# BoundaryController.net
KiCad netlist of a schematic drawn in EAGLE
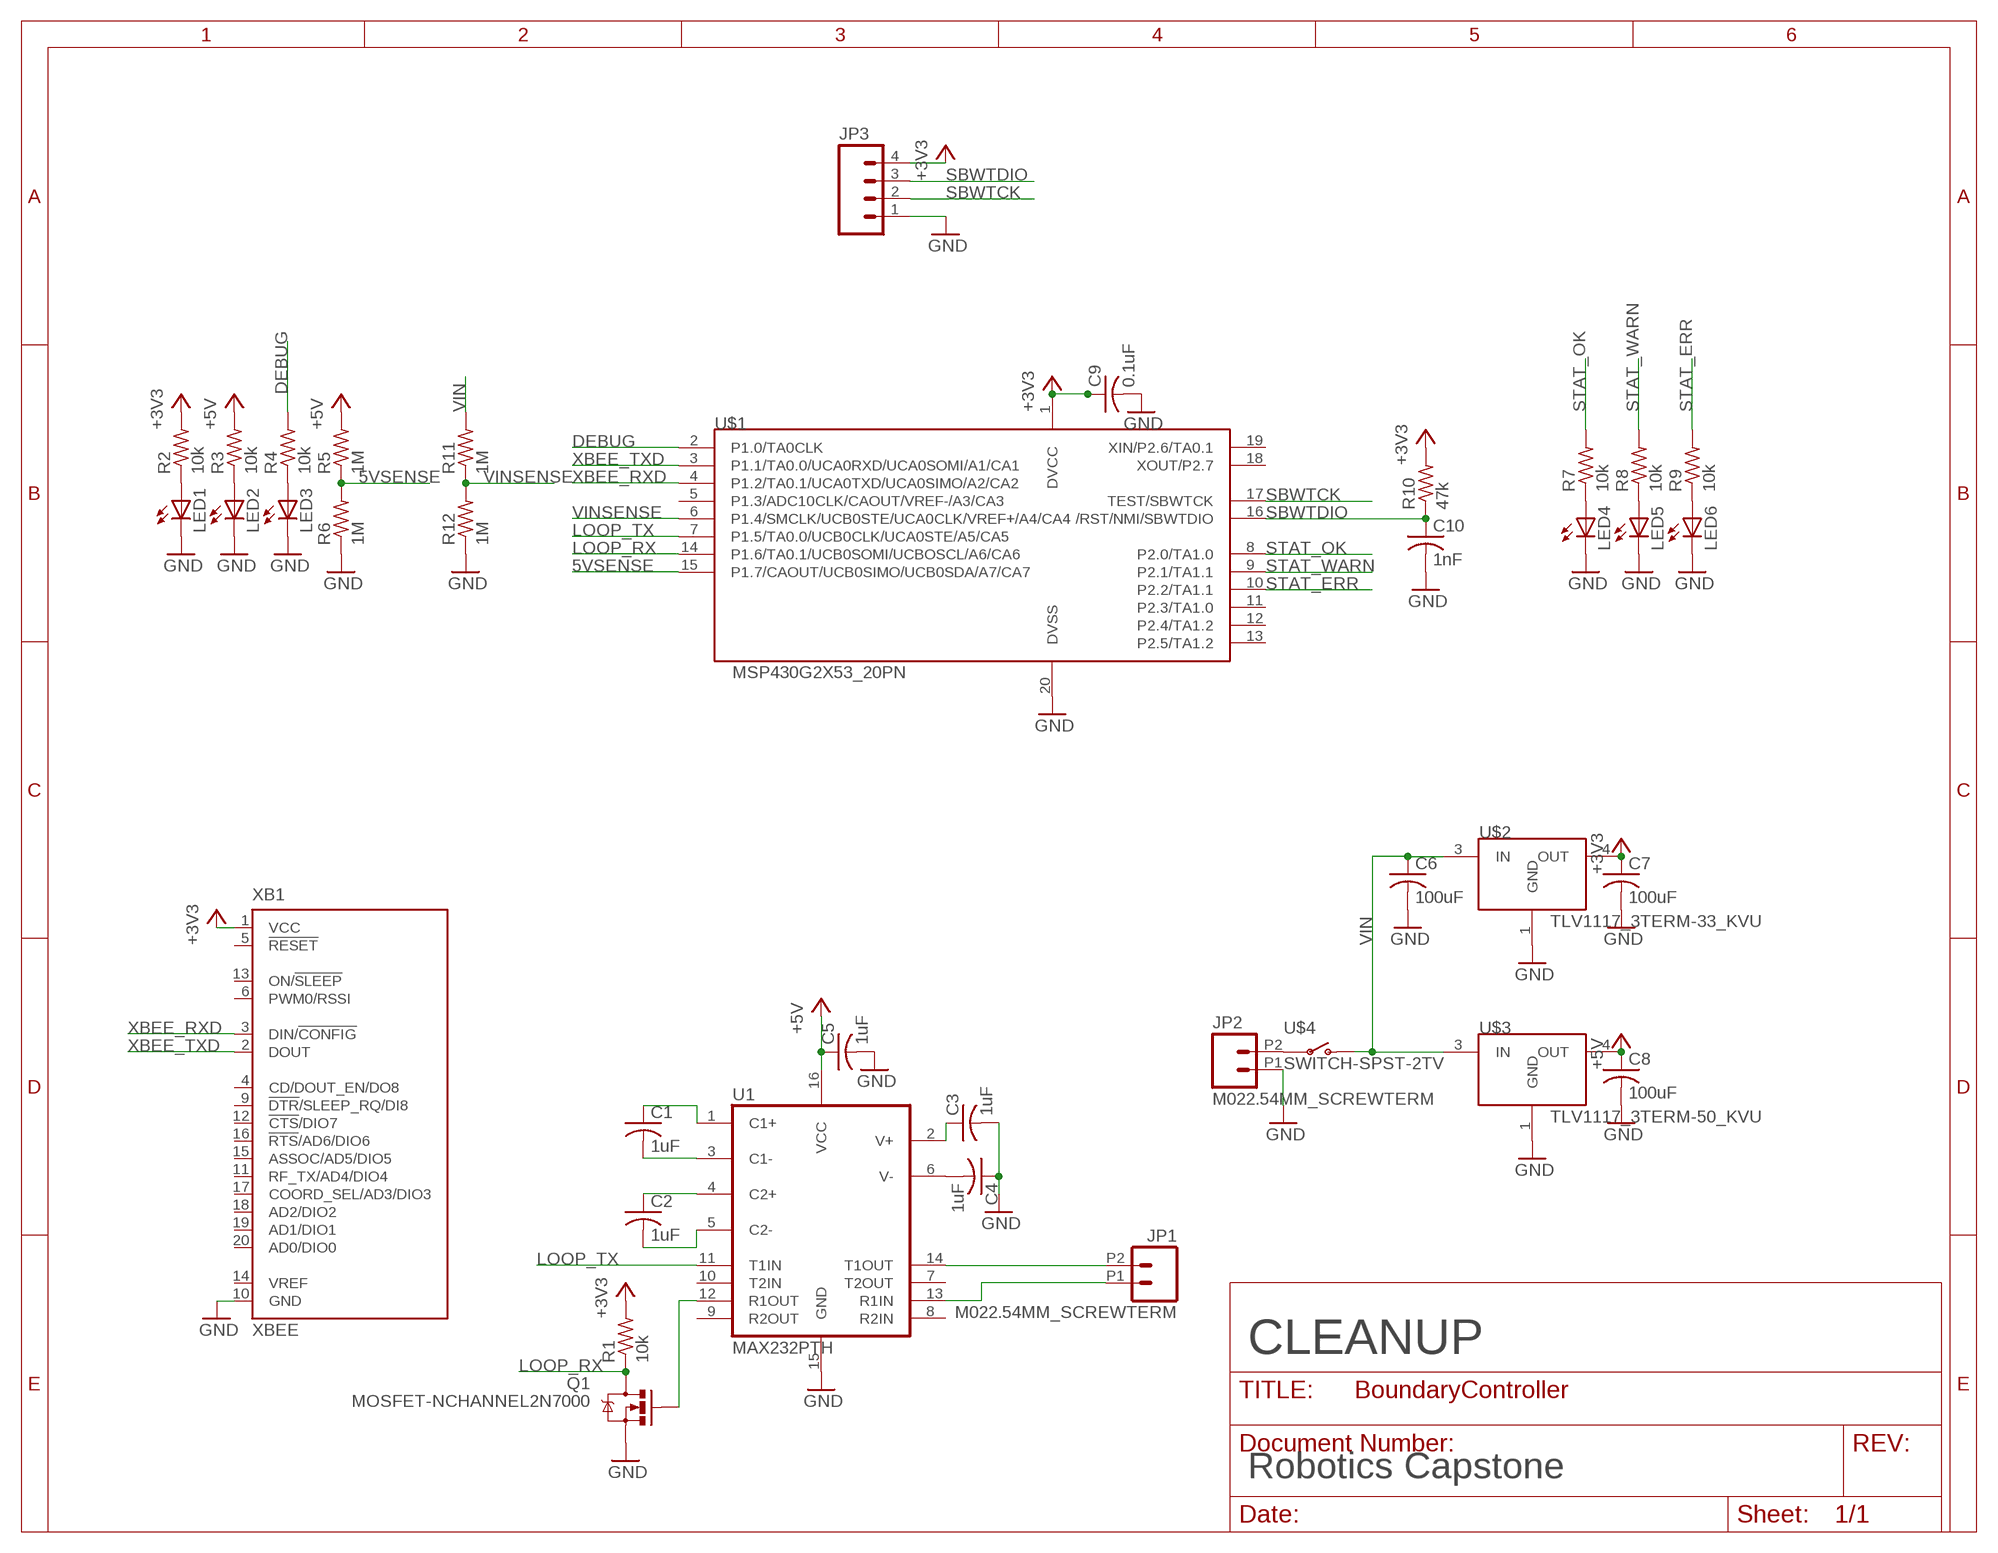
[diagram p0: schematic, sheet 1]

(export (version "E")
  (design (tool "Eeschema 10.0.6"))
  (components
    (comp (ref "C1")
      (value "1uF")
      (footprint "eagle-import:C0603")
      (libsource (lib "eagle-import") (part "C-USC0603"))
    )
    (comp (ref "C2")
      (value "1uF")
      (footprint "eagle-import:C0603")
      (libsource (lib "eagle-import") (part "C-USC0603"))
    )
    (comp (ref "C3")
      (value "1uF")
      (footprint "eagle-import:C0603")
      (libsource (lib "eagle-import") (part "C-USC0603"))
    )
    (comp (ref "C4")
      (value "1uF")
      (footprint "eagle-import:C0603")
      (libsource (lib "eagle-import") (part "C-USC0603"))
    )
    (comp (ref "C5")
      (value "1uF")
      (footprint "eagle-import:C0603")
      (libsource (lib "eagle-import") (part "C-USC0603"))
    )
    (comp (ref "C6")
      (value "100uF")
      (footprint "eagle-import:C0603")
      (libsource (lib "eagle-import") (part "C-USC0603"))
    )
    (comp (ref "C7")
      (value "100uF")
      (footprint "eagle-import:C0603")
      (libsource (lib "eagle-import") (part "C-USC0603"))
    )
    (comp (ref "C8")
      (value "100uF")
      (footprint "eagle-import:C0603")
      (libsource (lib "eagle-import") (part "C-USC0603"))
    )
    (comp (ref "C9")
      (value "0.1uF")
      (footprint "eagle-import:C0603")
      (libsource (lib "eagle-import") (part "C-USC0603"))
    )
    (comp (ref "C10")
      (value "1nF")
      (footprint "eagle-import:C0603")
      (libsource (lib "eagle-import") (part "C-USC0603"))
    )
    (comp (ref "JP1")
      (value "M022.54MM_SCREWTERM")
      (footprint "eagle-import:1X02_2.54_SCREWTERM")
      (libsource (lib "eagle-import") (part "M022.54MM_SCREWTERM"))
    )
    (comp (ref "JP2")
      (value "M022.54MM_SCREWTERM")
      (footprint "eagle-import:1X02_2.54_SCREWTERM")
      (libsource (lib "eagle-import") (part "M022.54MM_SCREWTERM"))
    )
    (comp (ref "JP3")
      (value "M04PTH")
      (footprint "eagle-import:1X04")
      (libsource (lib "eagle-import") (part "M04PTH"))
    )
    (comp (ref "LED1")
      (value "LED3MM")
      (footprint "eagle-import:LED3MM")
      (libsource (lib "eagle-import") (part "LED3MM"))
    )
    (comp (ref "LED2")
      (value "LED3MM")
      (footprint "eagle-import:LED3MM")
      (libsource (lib "eagle-import") (part "LED3MM"))
    )
    (comp (ref "LED3")
      (value "LED3MM")
      (footprint "eagle-import:LED3MM")
      (libsource (lib "eagle-import") (part "LED3MM"))
    )
    (comp (ref "LED4")
      (value "LED3MM")
      (footprint "eagle-import:LED3MM")
      (libsource (lib "eagle-import") (part "LED3MM"))
    )
    (comp (ref "LED5")
      (value "LED3MM")
      (footprint "eagle-import:LED3MM")
      (libsource (lib "eagle-import") (part "LED3MM"))
    )
    (comp (ref "LED6")
      (value "LED3MM")
      (footprint "eagle-import:LED3MM")
      (libsource (lib "eagle-import") (part "LED3MM"))
    )
    (comp (ref "Q1")
      (value "MOSFET-NCHANNEL2N7000")
      (footprint "eagle-import:TO-92")
      (libsource (lib "eagle-import") (part "MOSFET-NCHANNEL2N7000"))
    )
    (comp (ref "R1")
      (value "10k")
      (footprint "eagle-import:R0603")
      (libsource (lib "eagle-import") (part "R-US_R0603"))
    )
    (comp (ref "R2")
      (value "10k")
      (footprint "eagle-import:R0603")
      (libsource (lib "eagle-import") (part "R-US_R0603"))
    )
    (comp (ref "R3")
      (value "10k")
      (footprint "eagle-import:R0603")
      (libsource (lib "eagle-import") (part "R-US_R0603"))
    )
    (comp (ref "R4")
      (value "10k")
      (footprint "eagle-import:R0603")
      (libsource (lib "eagle-import") (part "R-US_R0603"))
    )
    (comp (ref "R5")
      (value "1M")
      (footprint "eagle-import:R0603")
      (libsource (lib "eagle-import") (part "R-US_R0603"))
    )
    (comp (ref "R6")
      (value "1M")
      (footprint "eagle-import:R0603")
      (libsource (lib "eagle-import") (part "R-US_R0603"))
    )
    (comp (ref "R7")
      (value "10k")
      (footprint "eagle-import:R0603")
      (libsource (lib "eagle-import") (part "R-US_R0603"))
    )
    (comp (ref "R8")
      (value "10k")
      (footprint "eagle-import:R0603")
      (libsource (lib "eagle-import") (part "R-US_R0603"))
    )
    (comp (ref "R9")
      (value "10k")
      (footprint "eagle-import:R0603")
      (libsource (lib "eagle-import") (part "R-US_R0603"))
    )
    (comp (ref "R10")
      (value "47k")
      (footprint "eagle-import:R0603")
      (libsource (lib "eagle-import") (part "R-US_R0603"))
    )
    (comp (ref "R11")
      (value "1M")
      (footprint "eagle-import:R0603")
      (libsource (lib "eagle-import") (part "R-US_R0603"))
    )
    (comp (ref "R12")
      (value "1M")
      (footprint "eagle-import:R0603")
      (libsource (lib "eagle-import") (part "R-US_R0603"))
    )
    (comp (ref "U$1")
      (value "MSP430G2X53_20PN")
      (footprint "eagle-import:DIL20")
      (libsource (lib "eagle-import") (part "MSP430G2X53_20PN"))
    )
    (comp (ref "U$2")
      (value "TLV1117_3TERM-33_KVU")
      (footprint "eagle-import:TI_TO-252_KVU_R-PSFM-G3")
      (libsource (lib "eagle-import") (part "TLV1117_3TERM-33_KVU"))
    )
    (comp (ref "U$3")
      (value "TLV1117_3TERM-50_KVU")
      (footprint "eagle-import:TI_TO-252_KVU_R-PSFM-G3")
      (libsource (lib "eagle-import") (part "TLV1117_3TERM-50_KVU"))
    )
    (comp (ref "U$4")
      (value "SWITCH-SPST-2TV")
      (footprint "eagle-import:SWITCH-SPST-VERTICAL")
      (libsource (lib "eagle-import") (part "SWITCH-SPST-2TV"))
    )
    (comp (ref "U1")
      (value "MAX232PTH")
      (footprint "eagle-import:DIL16")
      (libsource (lib "eagle-import") (part "MAX232PTH"))
    )
    (comp (ref "XB1")
      (value "XBEE")
      (footprint "eagle-import:XBEE")
      (libsource (lib "eagle-import") (part "XBEE"))
    )
  )
  (nets
    (net (code "1") (name "+3V3") (class "Default")
      (node (ref "C7") (pin "1") (pinfunction "1_1") (pintype "passive"))
      (node (ref "C9") (pin "1") (pinfunction "1_1") (pintype "passive"))
      (node (ref "JP3") (pin "4") (pinfunction "4_4") (pintype "passive"))
      (node (ref "R1") (pin "2") (pinfunction "2_2") (pintype "passive"))
      (node (ref "R10") (pin "2") (pinfunction "2_2") (pintype "passive"))
      (node (ref "R2") (pin "2") (pinfunction "2_2") (pintype "passive"))
      (node (ref "U$1") (pin "1") (pinfunction "DVCC_1") (pintype "bidirectional"))
      (node (ref "U$2") (pin "4") (pinfunction "OUT_4") (pintype "bidirectional"))
      (node (ref "XB1") (pin "1") (pinfunction "VCC_1") (pintype "power_in"))
    )
    (net (code "2") (name "+5V") (class "Default")
      (node (ref "C5") (pin "1") (pinfunction "1_1") (pintype "passive"))
      (node (ref "C8") (pin "1") (pinfunction "1_1") (pintype "passive"))
      (node (ref "R3") (pin "2") (pinfunction "2_2") (pintype "passive"))
      (node (ref "R5") (pin "2") (pinfunction "2_2") (pintype "passive"))
      (node (ref "U$3") (pin "4") (pinfunction "OUT_4") (pintype "bidirectional"))
      (node (ref "U1") (pin "16") (pinfunction "VCC_16") (pintype "bidirectional"))
    )
    (net (code "3") (name "/5VSENSE") (class "Default")
      (node (ref "R5") (pin "1") (pinfunction "1_1") (pintype "passive"))
      (node (ref "R6") (pin "2") (pinfunction "2_2") (pintype "passive"))
      (node (ref "U$1") (pin "15") (pinfunction "P1.7/CAOUT/UCB0SIMO/UCB0SDA/A7/CA7_15") (pintype "bidirectional"))
    )
    (net (code "4") (name "/DEBUG") (class "Default")
      (node (ref "R4") (pin "2") (pinfunction "2_2") (pintype "passive"))
      (node (ref "U$1") (pin "2") (pinfunction "P1.0/TA0CLK_2") (pintype "bidirectional"))
    )
    (net (code "5") (name "/LOOP_RX") (class "Default")
      (node (ref "Q1") (pin "3") (pinfunction "D_3") (pintype "passive"))
      (node (ref "R1") (pin "1") (pinfunction "1_1") (pintype "passive"))
      (node (ref "U$1") (pin "14") (pinfunction "P1.6/TA0.1/UCB0SOMI/UCBOSCL/A6/CA6_14") (pintype "bidirectional"))
    )
    (net (code "6") (name "/LOOP_TX") (class "Default")
      (node (ref "U$1") (pin "7") (pinfunction "P1.5/TA0.0/UCB0CLK/UCA0STE/A5/CA5_7") (pintype "bidirectional"))
      (node (ref "U1") (pin "11") (pinfunction "T1IN_11") (pintype "input"))
    )
    (net (code "7") (name "/SBWTCK") (class "Default")
      (node (ref "JP3") (pin "2") (pinfunction "2_2") (pintype "passive"))
      (node (ref "U$1") (pin "17") (pinfunction "TEST/SBWTCK_17") (pintype "bidirectional"))
    )
    (net (code "8") (name "/SBWTDIO") (class "Default")
      (node (ref "C10") (pin "1") (pinfunction "1_1") (pintype "passive"))
      (node (ref "JP3") (pin "3") (pinfunction "3_3") (pintype "passive"))
      (node (ref "R10") (pin "1") (pinfunction "1_1") (pintype "passive"))
      (node (ref "U$1") (pin "16") (pinfunction "/RST/NMI/SBWTDIO_16") (pintype "bidirectional"))
    )
    (net (code "9") (name "/STAT_ERR") (class "Default")
      (node (ref "R9") (pin "2") (pinfunction "2_2") (pintype "passive"))
      (node (ref "U$1") (pin "10") (pinfunction "P2.2/TA1.1_10") (pintype "bidirectional"))
    )
    (net (code "10") (name "/STAT_OK") (class "Default")
      (node (ref "R7") (pin "2") (pinfunction "2_2") (pintype "passive"))
      (node (ref "U$1") (pin "8") (pinfunction "P2.0/TA1.0_8") (pintype "bidirectional"))
    )
    (net (code "11") (name "/STAT_WARN") (class "Default")
      (node (ref "R8") (pin "2") (pinfunction "2_2") (pintype "passive"))
      (node (ref "U$1") (pin "9") (pinfunction "P2.1/TA1.1_9") (pintype "bidirectional"))
    )
    (net (code "12") (name "/VIN") (class "Default")
      (node (ref "C6") (pin "1") (pinfunction "1_1") (pintype "passive"))
      (node (ref "R11") (pin "2") (pinfunction "2_2") (pintype "passive"))
      (node (ref "U$2") (pin "3") (pinfunction "IN_3") (pintype "bidirectional"))
      (node (ref "U$3") (pin "3") (pinfunction "IN_3") (pintype "bidirectional"))
      (node (ref "U$4") (pin "1") (pinfunction "O_1") (pintype "passive"))
    )
    (net (code "13") (name "/VINSENSE") (class "Default")
      (node (ref "R11") (pin "1") (pinfunction "1_1") (pintype "passive"))
      (node (ref "R12") (pin "2") (pinfunction "2_2") (pintype "passive"))
      (node (ref "U$1") (pin "6") (pinfunction "P1.4/SMCLK/UCB0STE/UCA0CLK/VREF+/A4/CA4_6") (pintype "bidirectional"))
    )
    (net (code "14") (name "/XBEE_RXD") (class "Default")
      (node (ref "U$1") (pin "4") (pinfunction "P1.2/TA0.1/UCA0TXD/UCA0SIMO/A2/CA2_4") (pintype "bidirectional"))
      (node (ref "XB1") (pin "3") (pinfunction "DIN/~{CONFIG}_3") (pintype "input"))
    )
    (net (code "15") (name "/XBEE_TXD") (class "Default")
      (node (ref "U$1") (pin "3") (pinfunction "P1.1/TA0.0/UCA0RXD/UCA0SOMI/A1/CA1_3") (pintype "bidirectional"))
      (node (ref "XB1") (pin "2") (pinfunction "DOUT_2") (pintype "output"))
    )
    (net (code "16") (name "GND") (class "Default")
      (node (ref "C10") (pin "2") (pinfunction "2_2") (pintype "passive"))
      (node (ref "C3") (pin "2") (pinfunction "2_2") (pintype "passive"))
      (node (ref "C4") (pin "1") (pinfunction "1_1") (pintype "passive"))
      (node (ref "C5") (pin "2") (pinfunction "2_2") (pintype "passive"))
      (node (ref "C6") (pin "2") (pinfunction "2_2") (pintype "passive"))
      (node (ref "C7") (pin "2") (pinfunction "2_2") (pintype "passive"))
      (node (ref "C8") (pin "2") (pinfunction "2_2") (pintype "passive"))
      (node (ref "C9") (pin "2") (pinfunction "2_2") (pintype "passive"))
      (node (ref "JP2") (pin "P1") (pinfunction "1_P1") (pintype "passive"))
      (node (ref "JP3") (pin "1") (pinfunction "1_1") (pintype "passive"))
      (node (ref "LED1") (pin "K") (pinfunction "C_K") (pintype "passive"))
      (node (ref "LED2") (pin "K") (pinfunction "C_K") (pintype "passive"))
      (node (ref "LED3") (pin "K") (pinfunction "C_K") (pintype "passive"))
      (node (ref "LED4") (pin "K") (pinfunction "C_K") (pintype "passive"))
      (node (ref "LED5") (pin "K") (pinfunction "C_K") (pintype "passive"))
      (node (ref "LED6") (pin "K") (pinfunction "C_K") (pintype "passive"))
      (node (ref "Q1") (pin "1") (pinfunction "S_1") (pintype "passive"))
      (node (ref "R12") (pin "1") (pinfunction "1_1") (pintype "passive"))
      (node (ref "R6") (pin "1") (pinfunction "1_1") (pintype "passive"))
      (node (ref "U$1") (pin "20") (pinfunction "DVSS_20") (pintype "bidirectional"))
      (node (ref "U$2") (pin "1") (pinfunction "GND_1") (pintype "bidirectional"))
      (node (ref "U$3") (pin "1") (pinfunction "GND_1") (pintype "bidirectional"))
      (node (ref "U1") (pin "15") (pinfunction "GND_15") (pintype "bidirectional"))
      (node (ref "XB1") (pin "10") (pinfunction "GND_10") (pintype "power_in"))
    )
    (net (code "17") (name "Net-(JP1-1)") (class "Default")
      (node (ref "JP1") (pin "P1") (pinfunction "1_P1") (pintype "passive"))
      (node (ref "U1") (pin "13") (pinfunction "R1IN_13") (pintype "input"))
    )
    (net (code "18") (name "Net-(JP1-2)") (class "Default")
      (node (ref "JP1") (pin "P2") (pinfunction "2_P2") (pintype "passive"))
      (node (ref "U1") (pin "14") (pinfunction "T1OUT_14") (pintype "output"))
    )
    (net (code "19") (name "Net-(JP2-2)") (class "Default")
      (node (ref "JP2") (pin "P2") (pinfunction "2_P2") (pintype "passive"))
      (node (ref "U$4") (pin "2") (pinfunction "P_2") (pintype "passive"))
    )
    (net (code "20") (name "Net-(LED1-PadA)") (class "Default")
      (node (ref "LED1") (pin "A") (pinfunction "A_A") (pintype "passive"))
      (node (ref "R2") (pin "1") (pinfunction "1_1") (pintype "passive"))
    )
    (net (code "21") (name "Net-(LED2-PadA)") (class "Default")
      (node (ref "LED2") (pin "A") (pinfunction "A_A") (pintype "passive"))
      (node (ref "R3") (pin "1") (pinfunction "1_1") (pintype "passive"))
    )
    (net (code "22") (name "Net-(LED3-PadA)") (class "Default")
      (node (ref "LED3") (pin "A") (pinfunction "A_A") (pintype "passive"))
      (node (ref "R4") (pin "1") (pinfunction "1_1") (pintype "passive"))
    )
    (net (code "23") (name "Net-(LED4-PadA)") (class "Default")
      (node (ref "LED4") (pin "A") (pinfunction "A_A") (pintype "passive"))
      (node (ref "R7") (pin "1") (pinfunction "1_1") (pintype "passive"))
    )
    (net (code "24") (name "Net-(LED5-PadA)") (class "Default")
      (node (ref "LED5") (pin "A") (pinfunction "A_A") (pintype "passive"))
      (node (ref "R8") (pin "1") (pinfunction "1_1") (pintype "passive"))
    )
    (net (code "25") (name "Net-(LED6-PadA)") (class "Default")
      (node (ref "LED6") (pin "A") (pinfunction "A_A") (pintype "passive"))
      (node (ref "R9") (pin "1") (pinfunction "1_1") (pintype "passive"))
    )
    (net (code "26") (name "Net-(Q1-G)") (class "Default")
      (node (ref "Q1") (pin "2") (pinfunction "G_2") (pintype "passive"))
      (node (ref "U1") (pin "12") (pinfunction "R1OUT_12") (pintype "output"))
    )
    (net (code "27") (name "Net-(U1-C1+)") (class "Default")
      (node (ref "C1") (pin "1") (pinfunction "1_1") (pintype "passive"))
      (node (ref "U1") (pin "1") (pinfunction "C1+_1") (pintype "bidirectional"))
    )
    (net (code "28") (name "Net-(U1-C1-)") (class "Default")
      (node (ref "C1") (pin "2") (pinfunction "2_2") (pintype "passive"))
      (node (ref "U1") (pin "3") (pinfunction "C1-_3") (pintype "bidirectional"))
    )
    (net (code "29") (name "Net-(U1-C2+)") (class "Default")
      (node (ref "C2") (pin "1") (pinfunction "1_1") (pintype "passive"))
      (node (ref "U1") (pin "4") (pinfunction "C2+_4") (pintype "bidirectional"))
    )
    (net (code "30") (name "Net-(U1-C2-)") (class "Default")
      (node (ref "C2") (pin "2") (pinfunction "2_2") (pintype "passive"))
      (node (ref "U1") (pin "5") (pinfunction "C2-_5") (pintype "bidirectional"))
    )
    (net (code "31") (name "Net-(U1-V+)") (class "Default")
      (node (ref "C3") (pin "1") (pinfunction "1_1") (pintype "passive"))
      (node (ref "U1") (pin "2") (pinfunction "V+_2") (pintype "bidirectional"))
    )
    (net (code "32") (name "Net-(U1-V-)") (class "Default")
      (node (ref "C4") (pin "2") (pinfunction "2_2") (pintype "passive"))
      (node (ref "U1") (pin "6") (pinfunction "V-_6") (pintype "bidirectional"))
    )
    (net (code "33") (name "unconnected-(U$1-P1.3{slash}ADC10CLK{slash}CAOUT{slash}VREF-{slash}A3{slash}CA3-Pad5)") (class "Default")
      (node (ref "U$1") (pin "5") (pinfunction "P1.3/ADC10CLK/CAOUT/VREF-/A3/CA3_5") (pintype "bidirectional"))
    )
    (net (code "34") (name "unconnected-(U$1-P2.3{slash}TA1.0-Pad11)") (class "Default")
      (node (ref "U$1") (pin "11") (pinfunction "P2.3/TA1.0_11") (pintype "bidirectional"))
    )
    (net (code "35") (name "unconnected-(U$1-P2.4{slash}TA1.2-Pad12)") (class "Default")
      (node (ref "U$1") (pin "12") (pinfunction "P2.4/TA1.2_12") (pintype "bidirectional"))
    )
    (net (code "36") (name "unconnected-(U$1-P2.5{slash}TA1.2-Pad13)") (class "Default")
      (node (ref "U$1") (pin "13") (pinfunction "P2.5/TA1.2_13") (pintype "bidirectional"))
    )
    (net (code "37") (name "unconnected-(U$1-XIN{slash}P2.6{slash}TA0.1-Pad19)") (class "Default")
      (node (ref "U$1") (pin "19") (pinfunction "XIN/P2.6/TA0.1_19") (pintype "bidirectional"))
    )
    (net (code "38") (name "unconnected-(U$1-XOUT{slash}P2.7-Pad18)") (class "Default")
      (node (ref "U$1") (pin "18") (pinfunction "XOUT/P2.7_18") (pintype "bidirectional"))
    )
    (net (code "39") (name "unconnected-(U1-R2IN-Pad8)") (class "Default")
      (node (ref "U1") (pin "8") (pinfunction "R2IN_8") (pintype "input"))
    )
    (net (code "40") (name "unconnected-(U1-R2OUT-Pad9)") (class "Default")
      (node (ref "U1") (pin "9") (pinfunction "R2OUT_9") (pintype "output"))
    )
    (net (code "41") (name "unconnected-(U1-T2IN-Pad10)") (class "Default")
      (node (ref "U1") (pin "10") (pinfunction "T2IN_10") (pintype "input"))
    )
    (net (code "42") (name "unconnected-(U1-T2OUT-Pad7)") (class "Default")
      (node (ref "U1") (pin "7") (pinfunction "T2OUT_7") (pintype "output"))
    )
    (net (code "43") (name "unconnected-(XB1-AD0{slash}DIO0-Pad20)") (class "Default")
      (node (ref "XB1") (pin "20") (pinfunction "AD0/DIO0_20") (pintype "bidirectional"))
    )
    (net (code "44") (name "unconnected-(XB1-AD1{slash}DIO1-Pad19)") (class "Default")
      (node (ref "XB1") (pin "19") (pinfunction "AD1/DIO1_19") (pintype "bidirectional"))
    )
    (net (code "45") (name "unconnected-(XB1-AD2{slash}DIO2-Pad18)") (class "Default")
      (node (ref "XB1") (pin "18") (pinfunction "AD2/DIO2_18") (pintype "bidirectional"))
    )
    (net (code "46") (name "unconnected-(XB1-ASSOC{slash}AD5{slash}DIO5-Pad15)") (class "Default")
      (node (ref "XB1") (pin "15") (pinfunction "ASSOC/AD5/DIO5_15") (pintype "bidirectional"))
    )
    (net (code "47") (name "unconnected-(XB1-CD{slash}DOUT_EN{slash}DO8-Pad4)") (class "Default")
      (node (ref "XB1") (pin "4") (pinfunction "CD/DOUT_EN/DO8_4") (pintype "output"))
    )
    (net (code "48") (name "unconnected-(XB1-COORD_SEL{slash}AD3{slash}DIO3-Pad17)") (class "Default")
      (node (ref "XB1") (pin "17") (pinfunction "COORD_SEL/AD3/DIO3_17") (pintype "bidirectional"))
    )
    (net (code "49") (name "unconnected-(XB1-ON{slash}~{SLEEP}-Pad13)") (class "Default")
      (node (ref "XB1") (pin "13") (pinfunction "ON/~{SLEEP}_13") (pintype "output"))
    )
    (net (code "50") (name "unconnected-(XB1-PWM0{slash}RSSI-Pad6)") (class "Default")
      (node (ref "XB1") (pin "6") (pinfunction "PWM0/RSSI_6") (pintype "output"))
    )
    (net (code "51") (name "unconnected-(XB1-RF_TX{slash}AD4{slash}DIO4-Pad11)") (class "Default")
      (node (ref "XB1") (pin "11") (pinfunction "RF_TX/AD4/DIO4_11") (pintype "bidirectional"))
    )
    (net (code "52") (name "unconnected-(XB1-VREF-Pad14)") (class "Default")
      (node (ref "XB1") (pin "14") (pinfunction "VREF_14") (pintype "input"))
    )
    (net (code "53") (name "unconnected-(XB1-~{CTS}{slash}DIO7-Pad12)") (class "Default")
      (node (ref "XB1") (pin "12") (pinfunction "~{CTS}/DIO7_12") (pintype "bidirectional"))
    )
    (net (code "54") (name "unconnected-(XB1-~{DTR}{slash}SLEEP_RQ{slash}DI8-Pad9)") (class "Default")
      (node (ref "XB1") (pin "9") (pinfunction "~{DTR}/SLEEP_RQ/DI8_9") (pintype "bidirectional"))
    )
    (net (code "55") (name "unconnected-(XB1-~{RESET}-Pad5)") (class "Default")
      (node (ref "XB1") (pin "5") (pinfunction "~{RESET}_5") (pintype "input"))
    )
    (net (code "56") (name "unconnected-(XB1-~{RTS}{slash}AD6{slash}DIO6-Pad16)") (class "Default")
      (node (ref "XB1") (pin "16") (pinfunction "~{RTS}/AD6/DIO6_16") (pintype "bidirectional"))
    )
  )
)
